# Rectifi-Presicion.net
KiCad netlist of a schematic drawn in EAGLE
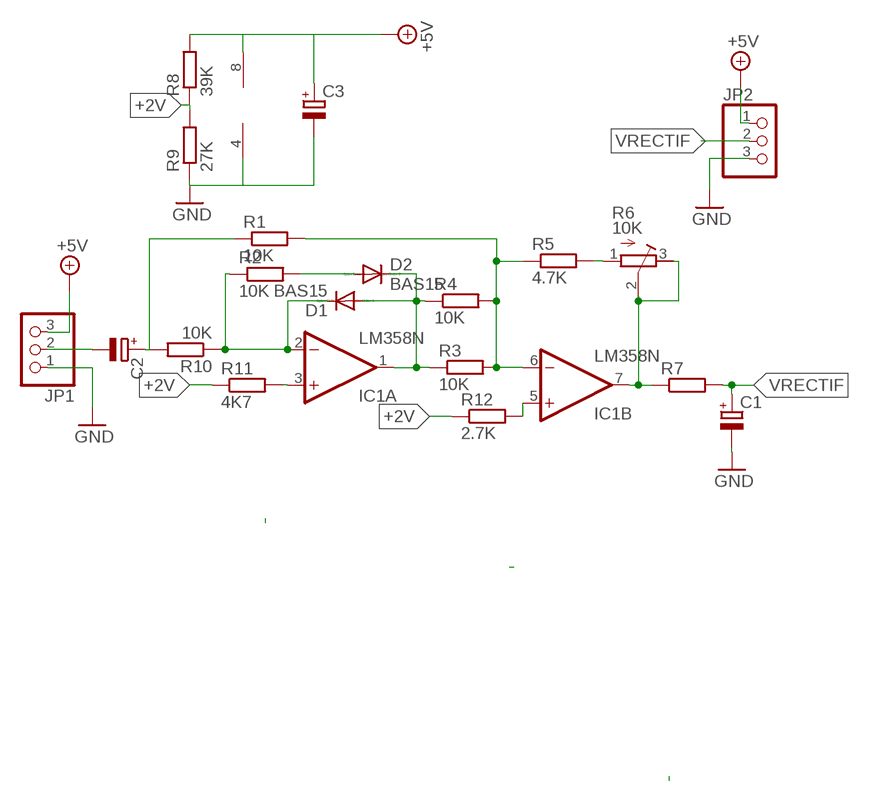
[diagram p0: schematic, sheet 1]

(export (version "E")
  (design (tool "Eeschema 10.0.6"))
  (components
    (comp (ref "C1")
      (value "CPOL-EUE2.5-5")
      (footprint "eagle-import:E2,5-5")
      (libsource (lib "eagle-import") (part "CPOL-EUE2.5-5"))
    )
    (comp (ref "C2")
      (value "CPOL-EUE2.5-5")
      (footprint "eagle-import:E2,5-5")
      (libsource (lib "eagle-import") (part "CPOL-EUE2.5-5"))
    )
    (comp (ref "C3")
      (value "CPOL-EUE2.5-6")
      (footprint "eagle-import:E2,5-6")
      (libsource (lib "eagle-import") (part "CPOL-EUE2.5-6"))
    )
    (comp (ref "D1")
      (value "BAS15")
      (footprint "eagle-import:DO34-7")
      (libsource (lib "eagle-import") (part "BAS15"))
    )
    (comp (ref "D2")
      (value "BAS15")
      (footprint "eagle-import:DO34-7")
      (libsource (lib "eagle-import") (part "BAS15"))
    )
    (comp (ref "IC1")
      (value "LM358N")
      (footprint "eagle-import:DIL08")
      (libsource (lib "eagle-import") (part "LM358N"))
    )
    (comp (ref "JP1")
      (value "PINHD-1X3")
      (footprint "eagle-import:1X03")
      (libsource (lib "eagle-import") (part "PINHD-1X3"))
    )
    (comp (ref "JP2")
      (value "PINHD-1X3")
      (footprint "eagle-import:1X03")
      (libsource (lib "eagle-import") (part "PINHD-1X3"))
    )
    (comp (ref "R1")
      (value "10K")
      (footprint "eagle-import:0207_7")
      (libsource (lib "eagle-import") (part "R-EU_0207/7"))
    )
    (comp (ref "R2")
      (value "10K")
      (footprint "eagle-import:0207_7")
      (libsource (lib "eagle-import") (part "R-EU_0207/7"))
    )
    (comp (ref "R3")
      (value "10K")
      (footprint "eagle-import:0207_7")
      (libsource (lib "eagle-import") (part "R-EU_0207/7"))
    )
    (comp (ref "R4")
      (value "10K")
      (footprint "eagle-import:0207_7")
      (libsource (lib "eagle-import") (part "R-EU_0207/7"))
    )
    (comp (ref "R5")
      (value "4.7K")
      (footprint "eagle-import:0207_7")
      (libsource (lib "eagle-import") (part "R-EU_0207/7"))
    )
    (comp (ref "R6")
      (value "10K")
      (footprint "eagle-import:RTRIM64W")
      (libsource (lib "eagle-import") (part "R-TRIMM64W"))
    )
    (comp (ref "R7")
      (value "R-EU_0207/7")
      (footprint "eagle-import:0207_7")
      (libsource (lib "eagle-import") (part "R-EU_0207/7"))
    )
    (comp (ref "R8")
      (value "39K")
      (footprint "eagle-import:0207_7")
      (libsource (lib "eagle-import") (part "R-EU_0207/7"))
    )
    (comp (ref "R9")
      (value "27K")
      (footprint "eagle-import:0207_7")
      (libsource (lib "eagle-import") (part "R-EU_0207/7"))
    )
    (comp (ref "R10")
      (value "10K")
      (footprint "eagle-import:0207_7")
      (libsource (lib "eagle-import") (part "R-EU_0207/7"))
    )
    (comp (ref "R11")
      (value "4K7")
      (footprint "eagle-import:0207_7")
      (libsource (lib "eagle-import") (part "R-EU_0207/7"))
    )
    (comp (ref "R12")
      (value "2.7K")
      (footprint "eagle-import:0207_7")
      (libsource (lib "eagle-import") (part "R-EU_0207/7"))
    )
  )
  (nets
    (net (code "1") (name "+2V") (class "Default")
      (node (ref "R11") (pin "1") (pinfunction "1_1") (pintype "passive"))
      (node (ref "R12") (pin "1") (pinfunction "1_1") (pintype "passive"))
      (node (ref "R8") (pin "1") (pinfunction "1_1") (pintype "passive"))
      (node (ref "R9") (pin "2") (pinfunction "2_2") (pintype "passive"))
    )
    (net (code "2") (name "+5V") (class "Default")
      (node (ref "C3") (pin "+") (pinfunction "+_+") (pintype "passive"))
      (node (ref "IC1") (pin "8") (pinfunction "V+_8") (pintype "power_in"))
      (node (ref "JP1") (pin "3") (pinfunction "3_3") (pintype "passive"))
      (node (ref "JP2") (pin "1") (pinfunction "1_1") (pintype "passive"))
      (node (ref "R8") (pin "2") (pinfunction "2_2") (pintype "passive"))
    )
    (net (code "3") (name "GND") (class "Default")
      (node (ref "C1") (pin "-") (pinfunction "-_-") (pintype "passive"))
      (node (ref "C3") (pin "-") (pinfunction "-_-") (pintype "passive"))
      (node (ref "IC1") (pin "4") (pinfunction "V-_4") (pintype "power_in"))
      (node (ref "JP1") (pin "1") (pinfunction "1_1") (pintype "passive"))
      (node (ref "JP2") (pin "3") (pinfunction "3_3") (pintype "passive"))
      (node (ref "R9") (pin "1") (pinfunction "1_1") (pintype "passive"))
    )
    (net (code "4") (name "Net-(C2-Pad+)") (class "Default")
      (node (ref "C2") (pin "+") (pinfunction "+_+") (pintype "passive"))
      (node (ref "R1") (pin "1") (pinfunction "1_1") (pintype "passive"))
      (node (ref "R10") (pin "2") (pinfunction "2_2") (pintype "passive"))
    )
    (net (code "5") (name "Net-(C2-Pad-)") (class "Default")
      (node (ref "C2") (pin "-") (pinfunction "-_-") (pintype "passive"))
      (node (ref "JP1") (pin "2") (pinfunction "2_2") (pintype "passive"))
    )
    (net (code "6") (name "Net-(D2-PadA)") (class "Default")
      (node (ref "D2") (pin "A") (pinfunction "A_A") (pintype "passive"))
      (node (ref "R2") (pin "2") (pinfunction "2_2") (pintype "passive"))
    )
    (net (code "7") (name "Net-(IC1A-+IN)") (class "Default")
      (node (ref "IC1") (pin "3") (pinfunction "+IN_3") (pintype "input"))
      (node (ref "R11") (pin "2") (pinfunction "2_2") (pintype "passive"))
    )
    (net (code "8") (name "Net-(IC1A--IN)") (class "Default")
      (node (ref "D1") (pin "C") (pinfunction "C_C") (pintype "passive"))
      (node (ref "IC1") (pin "2") (pinfunction "-IN_2") (pintype "input"))
      (node (ref "R10") (pin "1") (pinfunction "1_1") (pintype "passive"))
      (node (ref "R2") (pin "1") (pinfunction "1_1") (pintype "passive"))
    )
    (net (code "9") (name "Net-(IC1A-OUT)") (class "Default")
      (node (ref "D1") (pin "A") (pinfunction "A_A") (pintype "passive"))
      (node (ref "D2") (pin "C") (pinfunction "C_C") (pintype "passive"))
      (node (ref "IC1") (pin "1") (pinfunction "OUT_1") (pintype "output"))
      (node (ref "R3") (pin "1") (pinfunction "1_1") (pintype "passive"))
      (node (ref "R4") (pin "1") (pinfunction "1_1") (pintype "passive"))
    )
    (net (code "10") (name "Net-(IC1B-+IN)") (class "Default")
      (node (ref "IC1") (pin "5") (pinfunction "+IN_5") (pintype "input"))
      (node (ref "R12") (pin "2") (pinfunction "2_2") (pintype "passive"))
    )
    (net (code "11") (name "Net-(IC1B--IN)") (class "Default")
      (node (ref "IC1") (pin "6") (pinfunction "-IN_6") (pintype "input"))
      (node (ref "R1") (pin "2") (pinfunction "2_2") (pintype "passive"))
      (node (ref "R3") (pin "2") (pinfunction "2_2") (pintype "passive"))
      (node (ref "R4") (pin "2") (pinfunction "2_2") (pintype "passive"))
      (node (ref "R5") (pin "1") (pinfunction "1_1") (pintype "passive"))
    )
    (net (code "12") (name "Net-(IC1B-OUT)") (class "Default")
      (node (ref "IC1") (pin "7") (pinfunction "OUT_7") (pintype "output"))
      (node (ref "R6") (pin "2") (pinfunction "S_2") (pintype "passive"))
      (node (ref "R6") (pin "3") (pinfunction "E_3") (pintype "passive"))
      (node (ref "R7") (pin "1") (pinfunction "1_1") (pintype "passive"))
    )
    (net (code "13") (name "Net-(R6-A)") (class "Default")
      (node (ref "R5") (pin "2") (pinfunction "2_2") (pintype "passive"))
      (node (ref "R6") (pin "1") (pinfunction "A_1") (pintype "passive"))
    )
    (net (code "14") (name "VRECTIF") (class "Default")
      (node (ref "C1") (pin "+") (pinfunction "+_+") (pintype "passive"))
      (node (ref "JP2") (pin "2") (pinfunction "2_2") (pintype "passive"))
      (node (ref "R7") (pin "2") (pinfunction "2_2") (pintype "passive"))
    )
  )
)
